# bottom-breakout.net
KiCad netlist of a schematic drawn in EAGLE
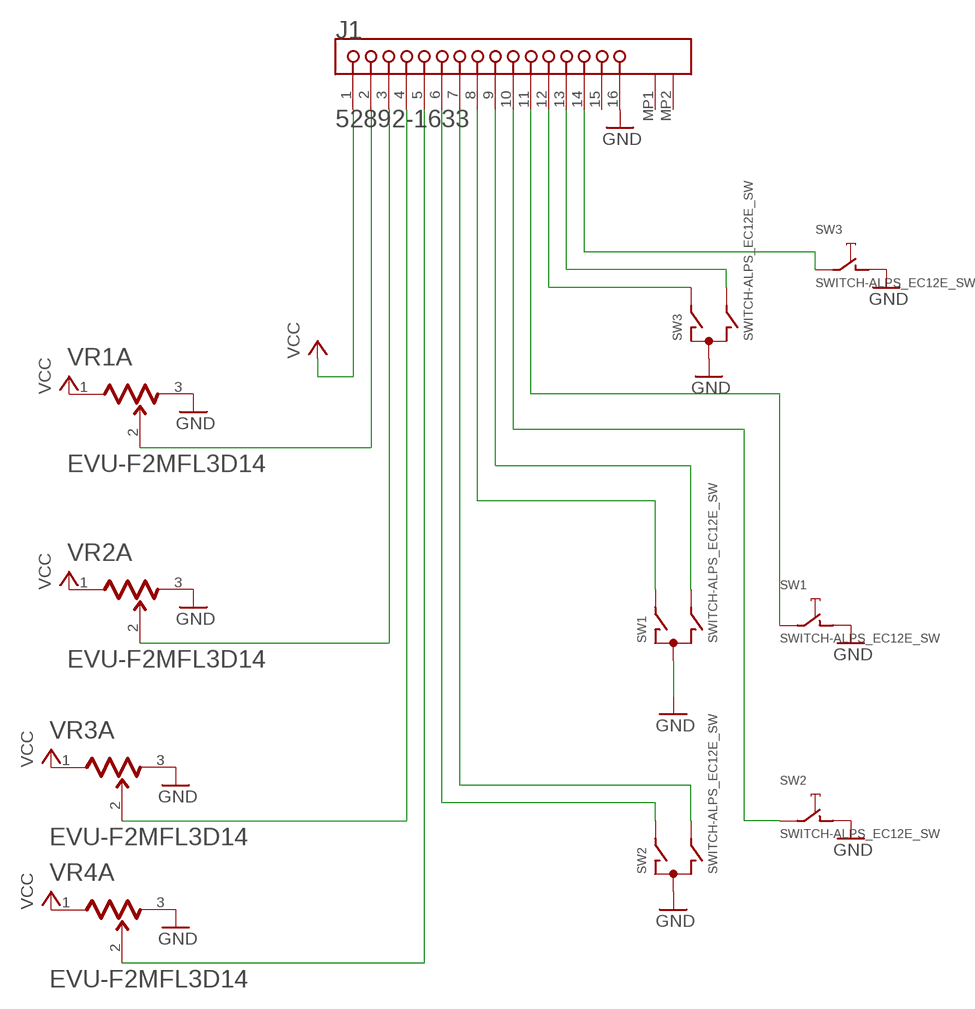
[diagram p0: schematic, sheet 1]

(export (version "E")
  (design (tool "Eeschema 10.0.6"))
  (components
    (comp (ref "J1")
      (value "MOLEX_52892-1633MOLEX_52892-1633_0_0")
      (footprint "eagle-import:MOLEX_52892-1633_0")
      (fields (field (name "MF") "Molex") (field (name "MPN") "52892-1633"))
      (libsource (lib "eagle-import") (part "MOLEX_52892-1633MOLEX_52892-1633_0_0"))
    )
    (comp (ref "SW1")
      (value "SWITCH-ALPS_EC12E_SW")
      (footprint "eagle-import:SWITCH-ALPS_ALPS_EC12E_SW")
      (fields (field (name "MPN") "EC12E2424407"))
      (libsource (lib "eagle-import") (part "SWITCH-ALPS_EC12E_SW"))
    )
    (comp (ref "SW2")
      (value "SWITCH-ALPS_EC12E_SW")
      (footprint "eagle-import:SWITCH-ALPS_ALPS_EC12E_SW")
      (fields (field (name "MPN") "EC12E2424407"))
      (libsource (lib "eagle-import") (part "SWITCH-ALPS_EC12E_SW"))
    )
    (comp (ref "SW3")
      (value "SWITCH-ALPS_EC12E_SW")
      (footprint "eagle-import:SWITCH-ALPS_ALPS_EC12E_SW")
      (fields (field (name "MPN") "EC12E2424407"))
      (libsource (lib "eagle-import") (part "SWITCH-ALPS_EC12E_SW"))
    )
    (comp (ref "VR1")
      (value "PANASONIC_EVU-F2MFL3D14PANASONIC_EVU-F2MFL3D14_0_0")
      (footprint "eagle-import:PANASONIC_EVU-F2MFL3D14_0")
      (fields
        (field (name "DIGIKEY_PART_NUMBER") "P3H8103-ND")
        (field (name "MF") "Panasonic")
        (field (name "MOUSER_PART_NUMBER") "667-EVU-F2MFL3D14")
      )
      (libsource (lib "eagle-import") (part "PANASONIC_EVU-F2MFL3D14PANASONIC_EVU-F2MFL3D14_0_0"))
    )
    (comp (ref "VR2")
      (value "PANASONIC_EVU-F2MFL3D14PANASONIC_EVU-F2MFL3D14_0_0")
      (footprint "eagle-import:PANASONIC_EVU-F2MFL3D14_0")
      (fields
        (field (name "DIGIKEY_PART_NUMBER") "P3H8103-ND")
        (field (name "MF") "Panasonic")
        (field (name "MOUSER_PART_NUMBER") "667-EVU-F2MFL3D14")
      )
      (libsource (lib "eagle-import") (part "PANASONIC_EVU-F2MFL3D14PANASONIC_EVU-F2MFL3D14_0_0"))
    )
    (comp (ref "VR3")
      (value "PANASONIC_EVU-F2MFL3D14PANASONIC_EVU-F2MFL3D14_0_0")
      (footprint "eagle-import:PANASONIC_EVU-F2MFL3D14_0")
      (fields
        (field (name "DIGIKEY_PART_NUMBER") "P3H8103-ND")
        (field (name "MF") "Panasonic")
        (field (name "MOUSER_PART_NUMBER") "667-EVU-F2MFL3D14")
      )
      (libsource (lib "eagle-import") (part "PANASONIC_EVU-F2MFL3D14PANASONIC_EVU-F2MFL3D14_0_0"))
    )
    (comp (ref "VR4")
      (value "PANASONIC_EVU-F2MFL3D14PANASONIC_EVU-F2MFL3D14_0_0")
      (footprint "eagle-import:PANASONIC_EVU-F2MFL3D14_0")
      (fields
        (field (name "DIGIKEY_PART_NUMBER") "P3H8103-ND")
        (field (name "MF") "Panasonic")
        (field (name "MOUSER_PART_NUMBER") "667-EVU-F2MFL3D14")
      )
      (libsource (lib "eagle-import") (part "PANASONIC_EVU-F2MFL3D14PANASONIC_EVU-F2MFL3D14_0_0"))
    )
  )
  (nets
    (net (code "1") (name "GND") (class "Default")
      (node (ref "J1") (pin "16") (pinfunction "16_16") (pintype "passive"))
      (node (ref "SW1") (pin "C") (pinfunction "C_C") (pintype "passive"))
      (node (ref "SW1") (pin "D") (pinfunction "1_D") (pintype "passive"))
      (node (ref "SW2") (pin "C") (pinfunction "C_C") (pintype "passive"))
      (node (ref "SW2") (pin "D") (pinfunction "1_D") (pintype "passive"))
      (node (ref "SW3") (pin "C") (pinfunction "C_C") (pintype "passive"))
      (node (ref "SW3") (pin "D") (pinfunction "1_D") (pintype "passive"))
      (node (ref "VR1") (pin "3") (pinfunction "3_3") (pintype "bidirectional"))
      (node (ref "VR2") (pin "3") (pinfunction "3_3") (pintype "bidirectional"))
      (node (ref "VR3") (pin "3") (pinfunction "3_3") (pintype "bidirectional"))
      (node (ref "VR4") (pin "3") (pinfunction "3_3") (pintype "bidirectional"))
    )
    (net (code "2") (name "Net-(J1-Pad2)") (class "Default")
      (node (ref "J1") (pin "2") (pinfunction "2_2") (pintype "passive"))
      (node (ref "VR1") (pin "2") (pinfunction "2_2") (pintype "bidirectional"))
    )
    (net (code "3") (name "Net-(J1-Pad3)") (class "Default")
      (node (ref "J1") (pin "3") (pinfunction "3_3") (pintype "passive"))
      (node (ref "VR2") (pin "2") (pinfunction "2_2") (pintype "bidirectional"))
    )
    (net (code "4") (name "Net-(J1-Pad4)") (class "Default")
      (node (ref "J1") (pin "4") (pinfunction "4_4") (pintype "passive"))
      (node (ref "VR3") (pin "2") (pinfunction "2_2") (pintype "bidirectional"))
    )
    (net (code "5") (name "Net-(J1-Pad5)") (class "Default")
      (node (ref "J1") (pin "5") (pinfunction "5_5") (pintype "passive"))
      (node (ref "VR4") (pin "2") (pinfunction "2_2") (pintype "bidirectional"))
    )
    (net (code "6") (name "Net-(J1-Pad6)") (class "Default")
      (node (ref "J1") (pin "6") (pinfunction "6_6") (pintype "passive"))
      (node (ref "SW2") (pin "A") (pinfunction "A_A") (pintype "passive"))
    )
    (net (code "7") (name "Net-(J1-Pad7)") (class "Default")
      (node (ref "J1") (pin "7") (pinfunction "7_7") (pintype "passive"))
      (node (ref "SW2") (pin "B") (pinfunction "B_B") (pintype "passive"))
    )
    (net (code "8") (name "Net-(J1-Pad8)") (class "Default")
      (node (ref "J1") (pin "8") (pinfunction "8_8") (pintype "passive"))
      (node (ref "SW1") (pin "A") (pinfunction "A_A") (pintype "passive"))
    )
    (net (code "9") (name "Net-(J1-Pad9)") (class "Default")
      (node (ref "J1") (pin "9") (pinfunction "9_9") (pintype "passive"))
      (node (ref "SW1") (pin "B") (pinfunction "B_B") (pintype "passive"))
    )
    (net (code "10") (name "Net-(J1-Pad12)") (class "Default")
      (node (ref "J1") (pin "12") (pinfunction "12_12") (pintype "passive"))
      (node (ref "SW3") (pin "A") (pinfunction "A_A") (pintype "passive"))
    )
    (net (code "11") (name "Net-(J1-Pad13)") (class "Default")
      (node (ref "J1") (pin "13") (pinfunction "13_13") (pintype "passive"))
      (node (ref "SW3") (pin "B") (pinfunction "B_B") (pintype "passive"))
    )
    (net (code "12") (name "Net-(SW1B-2)") (class "Default")
      (node (ref "J1") (pin "11") (pinfunction "11_11") (pintype "passive"))
      (node (ref "SW1") (pin "E") (pinfunction "2_E") (pintype "passive"))
    )
    (net (code "13") (name "Net-(SW2B-2)") (class "Default")
      (node (ref "J1") (pin "10") (pinfunction "10_10") (pintype "passive"))
      (node (ref "SW2") (pin "E") (pinfunction "2_E") (pintype "passive"))
    )
    (net (code "14") (name "Net-(SW3B-2)") (class "Default")
      (node (ref "J1") (pin "14") (pinfunction "14_14") (pintype "passive"))
      (node (ref "SW3") (pin "E") (pinfunction "2_E") (pintype "passive"))
    )
    (net (code "15") (name "VCC") (class "Default")
      (node (ref "J1") (pin "1") (pinfunction "1_1") (pintype "passive"))
      (node (ref "VR1") (pin "1") (pinfunction "1_1") (pintype "bidirectional"))
      (node (ref "VR2") (pin "1") (pinfunction "1_1") (pintype "bidirectional"))
      (node (ref "VR3") (pin "1") (pinfunction "1_1") (pintype "bidirectional"))
      (node (ref "VR4") (pin "1") (pinfunction "1_1") (pintype "bidirectional"))
    )
    (net (code "16") (name "unconnected-(J1-Pad15)") (class "Default")
      (node (ref "J1") (pin "15") (pinfunction "15_15") (pintype "passive"))
    )
    (net (code "17") (name "unconnected-(J1-PadMP1)") (class "Default")
      (node (ref "J1") (pin "MP1") (pinfunction "MP1_MP1") (pintype "passive"))
    )
    (net (code "18") (name "unconnected-(J1-PadMP2)") (class "Default")
      (node (ref "J1") (pin "MP2") (pinfunction "MP2_MP2") (pintype "passive"))
    )
  )
)
